# tangnano9k-bob-adapter2.net
KiCad netlist of a schematic drawn in EAGLE
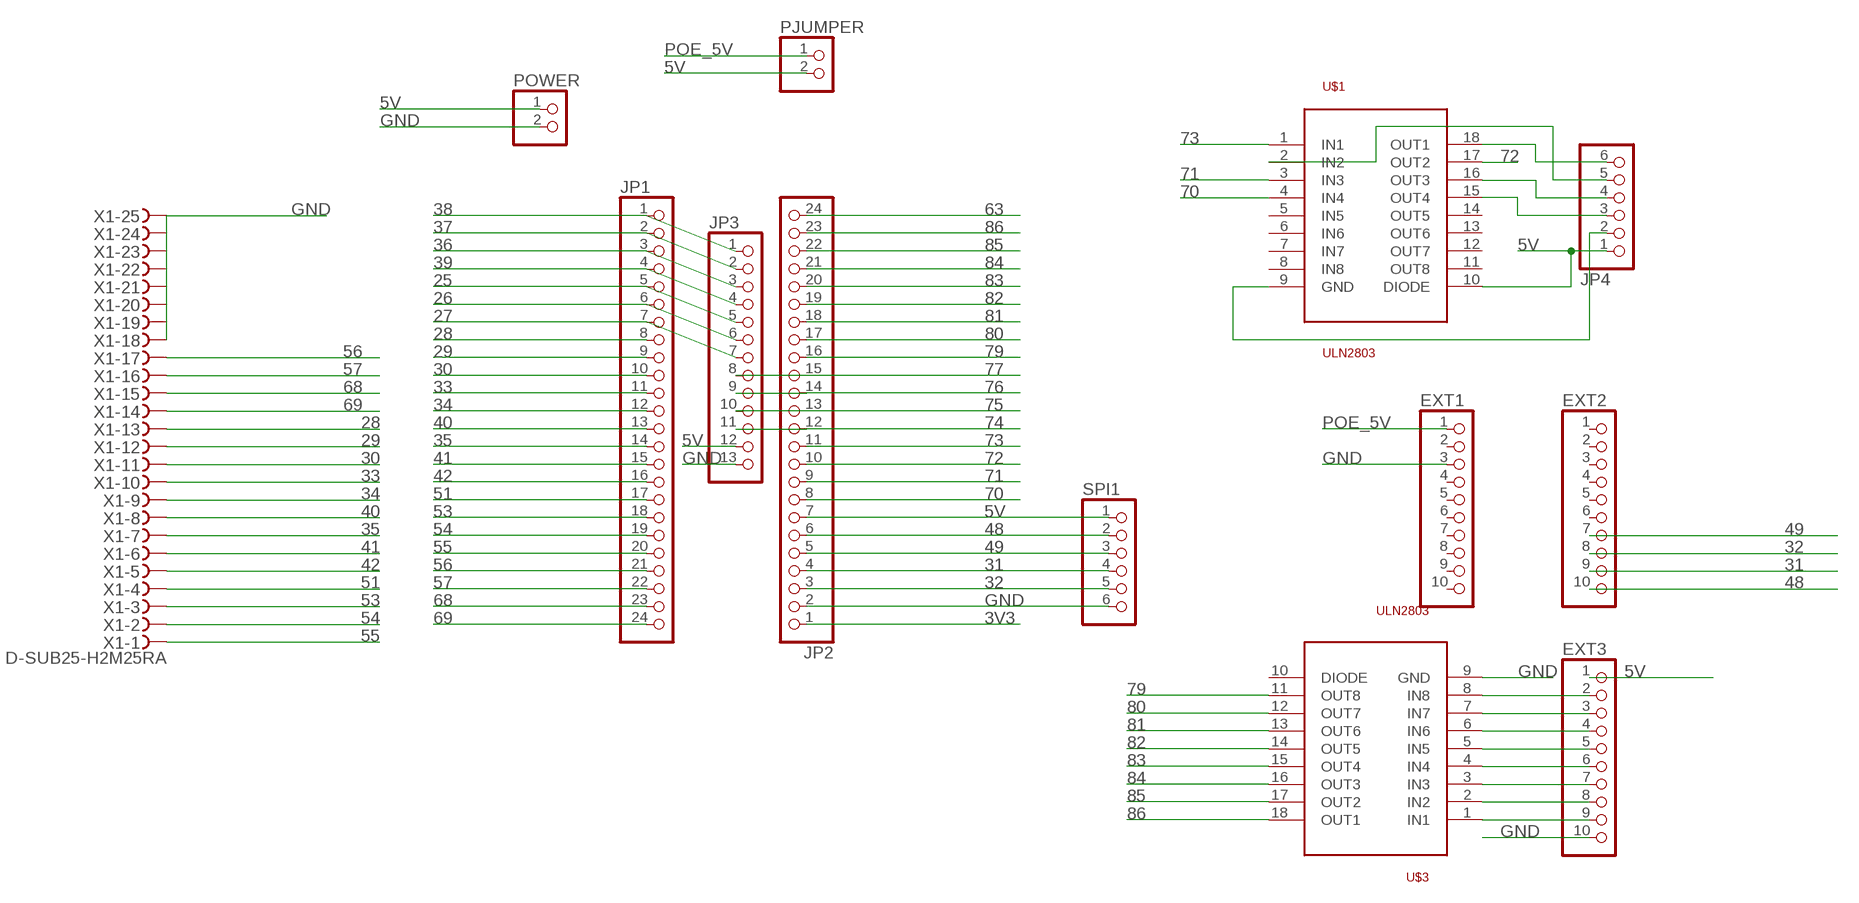
[diagram p0: schematic, sheet 1]

(export (version "E")
  (design (tool "Eeschema 10.0.6"))
  (components
    (comp (ref "EXT1")
      (value "PINHD-1X10")
      (footprint "eagle-import:1X10")
      (libsource (lib "eagle-import") (part "PINHD-1X10"))
    )
    (comp (ref "EXT2")
      (value "PINHD-1X10")
      (footprint "eagle-import:1X10")
      (libsource (lib "eagle-import") (part "PINHD-1X10"))
    )
    (comp (ref "EXT3")
      (value "PINHD-1X10")
      (footprint "eagle-import:1X10")
      (libsource (lib "eagle-import") (part "PINHD-1X10"))
    )
    (comp (ref "JP1")
      (value "PINHD-1X24")
      (footprint "eagle-import:1X24")
      (libsource (lib "eagle-import") (part "PINHD-1X24"))
    )
    (comp (ref "JP2")
      (value "PINHD-1X24")
      (footprint "eagle-import:1X24")
      (libsource (lib "eagle-import") (part "PINHD-1X24"))
    )
    (comp (ref "JP3")
      (value "PINHD-1X13")
      (footprint "eagle-import:1X13")
      (libsource (lib "eagle-import") (part "PINHD-1X13"))
    )
    (comp (ref "JP4")
      (value "PINHD-1X6/90")
      (footprint "eagle-import:1X06_90")
      (libsource (lib "eagle-import") (part "PINHD-1X6/90"))
    )
    (comp (ref "PJUMPER")
      (value "PINHD-1X2")
      (footprint "eagle-import:1X02")
      (libsource (lib "eagle-import") (part "PINHD-1X2"))
    )
    (comp (ref "POWER")
      (value "PINHD-1X2")
      (footprint "eagle-import:1X02")
      (libsource (lib "eagle-import") (part "PINHD-1X2"))
    )
    (comp (ref "SPI1")
      (value "PINHD-1X6")
      (footprint "eagle-import:1X06")
      (libsource (lib "eagle-import") (part "PINHD-1X6"))
    )
    (comp (ref "U$1")
      (value "ULN2803")
      (footprint "eagle-import:SO18L")
      (libsource (lib "eagle-import") (part "ULN2803"))
    )
    (comp (ref "U$3")
      (value "ULN2803")
      (footprint "eagle-import:SO18L")
      (libsource (lib "eagle-import") (part "ULN2803"))
    )
    (comp (ref "X1")
      (value "D-SUB25-H2M25RA")
      (footprint "eagle-import:H2M25RA")
      (libsource (lib "eagle-import") (part "D-SUB25-H2M25RA"))
    )
  )
  (nets
    (net (code "1") (name "/3V3") (class "Default")
      (node (ref "JP2") (pin "1") (pinfunction "1_1") (pintype "passive"))
    )
    (net (code "2") (name "/5V") (class "Default")
      (node (ref "EXT3") (pin "1") (pinfunction "1_1") (pintype "passive"))
      (node (ref "JP2") (pin "7") (pinfunction "7_7") (pintype "passive"))
      (node (ref "JP3") (pin "12") (pinfunction "12_12") (pintype "passive"))
      (node (ref "JP4") (pin "1") (pinfunction "1_1") (pintype "passive"))
      (node (ref "PJUMPER") (pin "2") (pinfunction "2_2") (pintype "passive"))
      (node (ref "POWER") (pin "1") (pinfunction "1_1") (pintype "passive"))
      (node (ref "SPI1") (pin "1") (pinfunction "1_1") (pintype "passive"))
      (node (ref "U$1") (pin "10") (pinfunction "DIODE_10") (pintype "power_in"))
    )
    (net (code "3") (name "/25") (class "Default")
      (node (ref "JP1") (pin "5") (pinfunction "5_5") (pintype "passive"))
      (node (ref "JP3") (pin "5") (pinfunction "5_5") (pintype "passive"))
    )
    (net (code "4") (name "/26") (class "Default")
      (node (ref "JP1") (pin "6") (pinfunction "6_6") (pintype "passive"))
      (node (ref "JP3") (pin "6") (pinfunction "6_6") (pintype "passive"))
    )
    (net (code "5") (name "/27") (class "Default")
      (node (ref "JP1") (pin "7") (pinfunction "7_7") (pintype "passive"))
      (node (ref "JP3") (pin "7") (pinfunction "7_7") (pintype "passive"))
    )
    (net (code "6") (name "/28") (class "Default")
      (node (ref "JP1") (pin "8") (pinfunction "8_8") (pintype "passive"))
      (node (ref "X1") (pin "13") (pinfunction "F_13") (pintype "passive"))
    )
    (net (code "7") (name "/29") (class "Default")
      (node (ref "JP1") (pin "9") (pinfunction "9_9") (pintype "passive"))
      (node (ref "X1") (pin "12") (pinfunction "F_12") (pintype "passive"))
    )
    (net (code "8") (name "/30") (class "Default")
      (node (ref "JP1") (pin "10") (pinfunction "10_10") (pintype "passive"))
      (node (ref "X1") (pin "11") (pinfunction "F_11") (pintype "passive"))
    )
    (net (code "9") (name "/31") (class "Default")
      (node (ref "EXT2") (pin "9") (pinfunction "9_9") (pintype "passive"))
      (node (ref "JP2") (pin "4") (pinfunction "4_4") (pintype "passive"))
      (node (ref "SPI1") (pin "4") (pinfunction "4_4") (pintype "passive"))
    )
    (net (code "10") (name "/32") (class "Default")
      (node (ref "EXT2") (pin "8") (pinfunction "8_8") (pintype "passive"))
      (node (ref "JP2") (pin "3") (pinfunction "3_3") (pintype "passive"))
      (node (ref "SPI1") (pin "5") (pinfunction "5_5") (pintype "passive"))
    )
    (net (code "11") (name "/33") (class "Default")
      (node (ref "JP1") (pin "11") (pinfunction "11_11") (pintype "passive"))
      (node (ref "X1") (pin "10") (pinfunction "F_10") (pintype "passive"))
    )
    (net (code "12") (name "/34") (class "Default")
      (node (ref "JP1") (pin "12") (pinfunction "12_12") (pintype "passive"))
      (node (ref "X1") (pin "9") (pinfunction "F_9") (pintype "passive"))
    )
    (net (code "13") (name "/35") (class "Default")
      (node (ref "JP1") (pin "14") (pinfunction "14_14") (pintype "passive"))
      (node (ref "X1") (pin "7") (pinfunction "F_7") (pintype "passive"))
    )
    (net (code "14") (name "/36") (class "Default")
      (node (ref "JP1") (pin "3") (pinfunction "3_3") (pintype "passive"))
      (node (ref "JP3") (pin "3") (pinfunction "3_3") (pintype "passive"))
    )
    (net (code "15") (name "/37") (class "Default")
      (node (ref "JP1") (pin "2") (pinfunction "2_2") (pintype "passive"))
      (node (ref "JP3") (pin "2") (pinfunction "2_2") (pintype "passive"))
    )
    (net (code "16") (name "/38") (class "Default")
      (node (ref "JP1") (pin "1") (pinfunction "1_1") (pintype "passive"))
      (node (ref "JP3") (pin "1") (pinfunction "1_1") (pintype "passive"))
    )
    (net (code "17") (name "/39") (class "Default")
      (node (ref "JP1") (pin "4") (pinfunction "4_4") (pintype "passive"))
      (node (ref "JP3") (pin "4") (pinfunction "4_4") (pintype "passive"))
    )
    (net (code "18") (name "/40") (class "Default")
      (node (ref "JP1") (pin "13") (pinfunction "13_13") (pintype "passive"))
      (node (ref "X1") (pin "8") (pinfunction "F_8") (pintype "passive"))
    )
    (net (code "19") (name "/41") (class "Default")
      (node (ref "JP1") (pin "15") (pinfunction "15_15") (pintype "passive"))
      (node (ref "X1") (pin "6") (pinfunction "F_6") (pintype "passive"))
    )
    (net (code "20") (name "/42") (class "Default")
      (node (ref "JP1") (pin "16") (pinfunction "16_16") (pintype "passive"))
      (node (ref "X1") (pin "5") (pinfunction "F_5") (pintype "passive"))
    )
    (net (code "21") (name "/48") (class "Default")
      (node (ref "EXT2") (pin "10") (pinfunction "10_10") (pintype "passive"))
      (node (ref "JP2") (pin "6") (pinfunction "6_6") (pintype "passive"))
      (node (ref "SPI1") (pin "2") (pinfunction "2_2") (pintype "passive"))
    )
    (net (code "22") (name "/49") (class "Default")
      (node (ref "EXT2") (pin "7") (pinfunction "7_7") (pintype "passive"))
      (node (ref "JP2") (pin "5") (pinfunction "5_5") (pintype "passive"))
      (node (ref "SPI1") (pin "3") (pinfunction "3_3") (pintype "passive"))
    )
    (net (code "23") (name "/51") (class "Default")
      (node (ref "JP1") (pin "17") (pinfunction "17_17") (pintype "passive"))
      (node (ref "X1") (pin "4") (pinfunction "F_4") (pintype "passive"))
    )
    (net (code "24") (name "/53") (class "Default")
      (node (ref "JP1") (pin "18") (pinfunction "18_18") (pintype "passive"))
      (node (ref "X1") (pin "3") (pinfunction "F_3") (pintype "passive"))
    )
    (net (code "25") (name "/54") (class "Default")
      (node (ref "JP1") (pin "19") (pinfunction "19_19") (pintype "passive"))
      (node (ref "X1") (pin "2") (pinfunction "F_2") (pintype "passive"))
    )
    (net (code "26") (name "/55") (class "Default")
      (node (ref "JP1") (pin "20") (pinfunction "20_20") (pintype "passive"))
      (node (ref "X1") (pin "1") (pinfunction "F_1") (pintype "passive"))
    )
    (net (code "27") (name "/56") (class "Default")
      (node (ref "JP1") (pin "21") (pinfunction "21_21") (pintype "passive"))
      (node (ref "X1") (pin "17") (pinfunction "F_17") (pintype "passive"))
    )
    (net (code "28") (name "/57") (class "Default")
      (node (ref "JP1") (pin "22") (pinfunction "22_22") (pintype "passive"))
      (node (ref "X1") (pin "16") (pinfunction "F_16") (pintype "passive"))
    )
    (net (code "29") (name "/63") (class "Default")
      (node (ref "JP2") (pin "24") (pinfunction "24_24") (pintype "passive"))
    )
    (net (code "30") (name "/68") (class "Default")
      (node (ref "JP1") (pin "23") (pinfunction "23_23") (pintype "passive"))
      (node (ref "X1") (pin "15") (pinfunction "F_15") (pintype "passive"))
    )
    (net (code "31") (name "/69") (class "Default")
      (node (ref "JP1") (pin "24") (pinfunction "24_24") (pintype "passive"))
      (node (ref "X1") (pin "14") (pinfunction "F_14") (pintype "passive"))
    )
    (net (code "32") (name "/70") (class "Default")
      (node (ref "JP2") (pin "8") (pinfunction "8_8") (pintype "passive"))
      (node (ref "U$1") (pin "4") (pinfunction "IN4_4") (pintype "input"))
    )
    (net (code "33") (name "/71") (class "Default")
      (node (ref "JP2") (pin "9") (pinfunction "9_9") (pintype "passive"))
      (node (ref "U$1") (pin "3") (pinfunction "IN3_3") (pintype "input"))
    )
    (net (code "34") (name "/72") (class "Default")
      (node (ref "JP2") (pin "10") (pinfunction "10_10") (pintype "passive"))
      (node (ref "U$1") (pin "17") (pinfunction "OUT2_17") (pintype "open_collector"))
    )
    (net (code "35") (name "/73") (class "Default")
      (node (ref "JP2") (pin "11") (pinfunction "11_11") (pintype "passive"))
      (node (ref "U$1") (pin "1") (pinfunction "IN1_1") (pintype "input"))
    )
    (net (code "36") (name "/74") (class "Default")
      (node (ref "JP2") (pin "12") (pinfunction "12_12") (pintype "passive"))
      (node (ref "JP3") (pin "11") (pinfunction "11_11") (pintype "passive"))
    )
    (net (code "37") (name "/75") (class "Default")
      (node (ref "JP2") (pin "13") (pinfunction "13_13") (pintype "passive"))
      (node (ref "JP3") (pin "10") (pinfunction "10_10") (pintype "passive"))
    )
    (net (code "38") (name "/76") (class "Default")
      (node (ref "JP2") (pin "14") (pinfunction "14_14") (pintype "passive"))
      (node (ref "JP3") (pin "9") (pinfunction "9_9") (pintype "passive"))
    )
    (net (code "39") (name "/77") (class "Default")
      (node (ref "JP2") (pin "15") (pinfunction "15_15") (pintype "passive"))
      (node (ref "JP3") (pin "8") (pinfunction "8_8") (pintype "passive"))
    )
    (net (code "40") (name "/79") (class "Default")
      (node (ref "JP2") (pin "16") (pinfunction "16_16") (pintype "passive"))
      (node (ref "U$3") (pin "11") (pinfunction "OUT8_11") (pintype "open_collector"))
    )
    (net (code "41") (name "/80") (class "Default")
      (node (ref "JP2") (pin "17") (pinfunction "17_17") (pintype "passive"))
      (node (ref "U$3") (pin "12") (pinfunction "OUT7_12") (pintype "open_collector"))
    )
    (net (code "42") (name "/81") (class "Default")
      (node (ref "JP2") (pin "18") (pinfunction "18_18") (pintype "passive"))
      (node (ref "U$3") (pin "13") (pinfunction "OUT6_13") (pintype "open_collector"))
    )
    (net (code "43") (name "/82") (class "Default")
      (node (ref "JP2") (pin "19") (pinfunction "19_19") (pintype "passive"))
      (node (ref "U$3") (pin "14") (pinfunction "OUT5_14") (pintype "open_collector"))
    )
    (net (code "44") (name "/83") (class "Default")
      (node (ref "JP2") (pin "20") (pinfunction "20_20") (pintype "passive"))
      (node (ref "U$3") (pin "15") (pinfunction "OUT4_15") (pintype "open_collector"))
    )
    (net (code "45") (name "/84") (class "Default")
      (node (ref "JP2") (pin "21") (pinfunction "21_21") (pintype "passive"))
      (node (ref "U$3") (pin "16") (pinfunction "OUT3_16") (pintype "open_collector"))
    )
    (net (code "46") (name "/85") (class "Default")
      (node (ref "JP2") (pin "22") (pinfunction "22_22") (pintype "passive"))
      (node (ref "U$3") (pin "17") (pinfunction "OUT2_17") (pintype "open_collector"))
    )
    (net (code "47") (name "/86") (class "Default")
      (node (ref "JP2") (pin "23") (pinfunction "23_23") (pintype "passive"))
      (node (ref "U$3") (pin "18") (pinfunction "OUT1_18") (pintype "open_collector"))
    )
    (net (code "48") (name "/DIODE") (class "Default")
      (node (ref "U$3") (pin "10") (pinfunction "DIODE_10") (pintype "power_in"))
    )
    (net (code "49") (name "/GND") (class "Default")
      (node (ref "EXT1") (pin "3") (pinfunction "3_3") (pintype "passive"))
      (node (ref "EXT3") (pin "10") (pinfunction "10_10") (pintype "passive"))
      (node (ref "JP2") (pin "2") (pinfunction "2_2") (pintype "passive"))
      (node (ref "JP3") (pin "13") (pinfunction "13_13") (pintype "passive"))
      (node (ref "JP4") (pin "2") (pinfunction "2_2") (pintype "passive"))
      (node (ref "POWER") (pin "2") (pinfunction "2_2") (pintype "passive"))
      (node (ref "SPI1") (pin "6") (pinfunction "6_6") (pintype "passive"))
      (node (ref "U$1") (pin "9") (pinfunction "GND_9") (pintype "power_in"))
      (node (ref "U$3") (pin "9") (pinfunction "GND_9") (pintype "power_in"))
      (node (ref "X1") (pin "18") (pinfunction "F_18") (pintype "passive"))
      (node (ref "X1") (pin "19") (pinfunction "F_19") (pintype "passive"))
      (node (ref "X1") (pin "20") (pinfunction "F_20") (pintype "passive"))
      (node (ref "X1") (pin "21") (pinfunction "F_21") (pintype "passive"))
      (node (ref "X1") (pin "22") (pinfunction "F_22") (pintype "passive"))
      (node (ref "X1") (pin "23") (pinfunction "F_23") (pintype "passive"))
      (node (ref "X1") (pin "24") (pinfunction "F_24") (pintype "passive"))
      (node (ref "X1") (pin "25") (pinfunction "F_25") (pintype "passive"))
    )
    (net (code "50") (name "/POE_5V") (class "Default")
      (node (ref "EXT1") (pin "1") (pinfunction "1_1") (pintype "passive"))
      (node (ref "PJUMPER") (pin "1") (pinfunction "1_1") (pintype "passive"))
    )
    (net (code "51") (name "Net-(U$1-IN2)") (class "Default")
      (node (ref "JP4") (pin "5") (pinfunction "5_5") (pintype "passive"))
      (node (ref "U$1") (pin "2") (pinfunction "IN2_2") (pintype "input"))
    )
    (net (code "52") (name "Net-(U$1-OUT1)") (class "Default")
      (node (ref "JP4") (pin "6") (pinfunction "6_6") (pintype "passive"))
      (node (ref "U$1") (pin "18") (pinfunction "OUT1_18") (pintype "open_collector"))
    )
    (net (code "53") (name "Net-(U$1-OUT3)") (class "Default")
      (node (ref "JP4") (pin "4") (pinfunction "4_4") (pintype "passive"))
      (node (ref "U$1") (pin "16") (pinfunction "OUT3_16") (pintype "open_collector"))
    )
    (net (code "54") (name "Net-(U$1-OUT4)") (class "Default")
      (node (ref "JP4") (pin "3") (pinfunction "3_3") (pintype "passive"))
      (node (ref "U$1") (pin "15") (pinfunction "OUT4_15") (pintype "open_collector"))
    )
    (net (code "55") (name "Net-(U$3-IN1)") (class "Default")
      (node (ref "EXT3") (pin "9") (pinfunction "9_9") (pintype "passive"))
      (node (ref "U$3") (pin "1") (pinfunction "IN1_1") (pintype "input"))
    )
    (net (code "56") (name "Net-(U$3-IN2)") (class "Default")
      (node (ref "EXT3") (pin "8") (pinfunction "8_8") (pintype "passive"))
      (node (ref "U$3") (pin "2") (pinfunction "IN2_2") (pintype "input"))
    )
    (net (code "57") (name "Net-(U$3-IN3)") (class "Default")
      (node (ref "EXT3") (pin "7") (pinfunction "7_7") (pintype "passive"))
      (node (ref "U$3") (pin "3") (pinfunction "IN3_3") (pintype "input"))
    )
    (net (code "58") (name "Net-(U$3-IN4)") (class "Default")
      (node (ref "EXT3") (pin "6") (pinfunction "6_6") (pintype "passive"))
      (node (ref "U$3") (pin "4") (pinfunction "IN4_4") (pintype "input"))
    )
    (net (code "59") (name "Net-(U$3-IN5)") (class "Default")
      (node (ref "EXT3") (pin "5") (pinfunction "5_5") (pintype "passive"))
      (node (ref "U$3") (pin "5") (pinfunction "IN5_5") (pintype "input"))
    )
    (net (code "60") (name "Net-(U$3-IN6)") (class "Default")
      (node (ref "EXT3") (pin "4") (pinfunction "4_4") (pintype "passive"))
      (node (ref "U$3") (pin "6") (pinfunction "IN6_6") (pintype "input"))
    )
    (net (code "61") (name "Net-(U$3-IN7)") (class "Default")
      (node (ref "EXT3") (pin "3") (pinfunction "3_3") (pintype "passive"))
      (node (ref "U$3") (pin "7") (pinfunction "IN7_7") (pintype "input"))
    )
    (net (code "62") (name "Net-(U$3-IN8)") (class "Default")
      (node (ref "EXT3") (pin "2") (pinfunction "2_2") (pintype "passive"))
      (node (ref "U$3") (pin "8") (pinfunction "IN8_8") (pintype "input"))
    )
    (net (code "63") (name "unconnected-(EXT1-Pad2)") (class "Default")
      (node (ref "EXT1") (pin "2") (pinfunction "2_2") (pintype "passive"))
    )
    (net (code "64") (name "unconnected-(EXT1-Pad4)") (class "Default")
      (node (ref "EXT1") (pin "4") (pinfunction "4_4") (pintype "passive"))
    )
    (net (code "65") (name "unconnected-(EXT1-Pad5)") (class "Default")
      (node (ref "EXT1") (pin "5") (pinfunction "5_5") (pintype "passive"))
    )
    (net (code "66") (name "unconnected-(EXT1-Pad6)") (class "Default")
      (node (ref "EXT1") (pin "6") (pinfunction "6_6") (pintype "passive"))
    )
    (net (code "67") (name "unconnected-(EXT1-Pad7)") (class "Default")
      (node (ref "EXT1") (pin "7") (pinfunction "7_7") (pintype "passive"))
    )
    (net (code "68") (name "unconnected-(EXT1-Pad8)") (class "Default")
      (node (ref "EXT1") (pin "8") (pinfunction "8_8") (pintype "passive"))
    )
    (net (code "69") (name "unconnected-(EXT1-Pad9)") (class "Default")
      (node (ref "EXT1") (pin "9") (pinfunction "9_9") (pintype "passive"))
    )
    (net (code "70") (name "unconnected-(EXT1-Pad10)") (class "Default")
      (node (ref "EXT1") (pin "10") (pinfunction "10_10") (pintype "passive"))
    )
    (net (code "71") (name "unconnected-(EXT2-Pad1)") (class "Default")
      (node (ref "EXT2") (pin "1") (pinfunction "1_1") (pintype "passive"))
    )
    (net (code "72") (name "unconnected-(EXT2-Pad2)") (class "Default")
      (node (ref "EXT2") (pin "2") (pinfunction "2_2") (pintype "passive"))
    )
    (net (code "73") (name "unconnected-(EXT2-Pad3)") (class "Default")
      (node (ref "EXT2") (pin "3") (pinfunction "3_3") (pintype "passive"))
    )
    (net (code "74") (name "unconnected-(EXT2-Pad4)") (class "Default")
      (node (ref "EXT2") (pin "4") (pinfunction "4_4") (pintype "passive"))
    )
    (net (code "75") (name "unconnected-(EXT2-Pad5)") (class "Default")
      (node (ref "EXT2") (pin "5") (pinfunction "5_5") (pintype "passive"))
    )
    (net (code "76") (name "unconnected-(EXT2-Pad6)") (class "Default")
      (node (ref "EXT2") (pin "6") (pinfunction "6_6") (pintype "passive"))
    )
    (net (code "77") (name "unconnected-(U$1-IN5-Pad5)") (class "Default")
      (node (ref "U$1") (pin "5") (pinfunction "IN5_5") (pintype "input"))
    )
    (net (code "78") (name "unconnected-(U$1-IN6-Pad6)") (class "Default")
      (node (ref "U$1") (pin "6") (pinfunction "IN6_6") (pintype "input"))
    )
    (net (code "79") (name "unconnected-(U$1-IN7-Pad7)") (class "Default")
      (node (ref "U$1") (pin "7") (pinfunction "IN7_7") (pintype "input"))
    )
    (net (code "80") (name "unconnected-(U$1-IN8-Pad8)") (class "Default")
      (node (ref "U$1") (pin "8") (pinfunction "IN8_8") (pintype "input"))
    )
    (net (code "81") (name "unconnected-(U$1-OUT5-Pad14)") (class "Default")
      (node (ref "U$1") (pin "14") (pinfunction "OUT5_14") (pintype "open_collector"))
    )
    (net (code "82") (name "unconnected-(U$1-OUT6-Pad13)") (class "Default")
      (node (ref "U$1") (pin "13") (pinfunction "OUT6_13") (pintype "open_collector"))
    )
    (net (code "83") (name "unconnected-(U$1-OUT7-Pad12)") (class "Default")
      (node (ref "U$1") (pin "12") (pinfunction "OUT7_12") (pintype "open_collector"))
    )
    (net (code "84") (name "unconnected-(U$1-OUT8-Pad11)") (class "Default")
      (node (ref "U$1") (pin "11") (pinfunction "OUT8_11") (pintype "open_collector"))
    )
  )
)
